# MOSFTET_Driver_block.net
KiCad netlist of a schematic drawn in Altium Designer
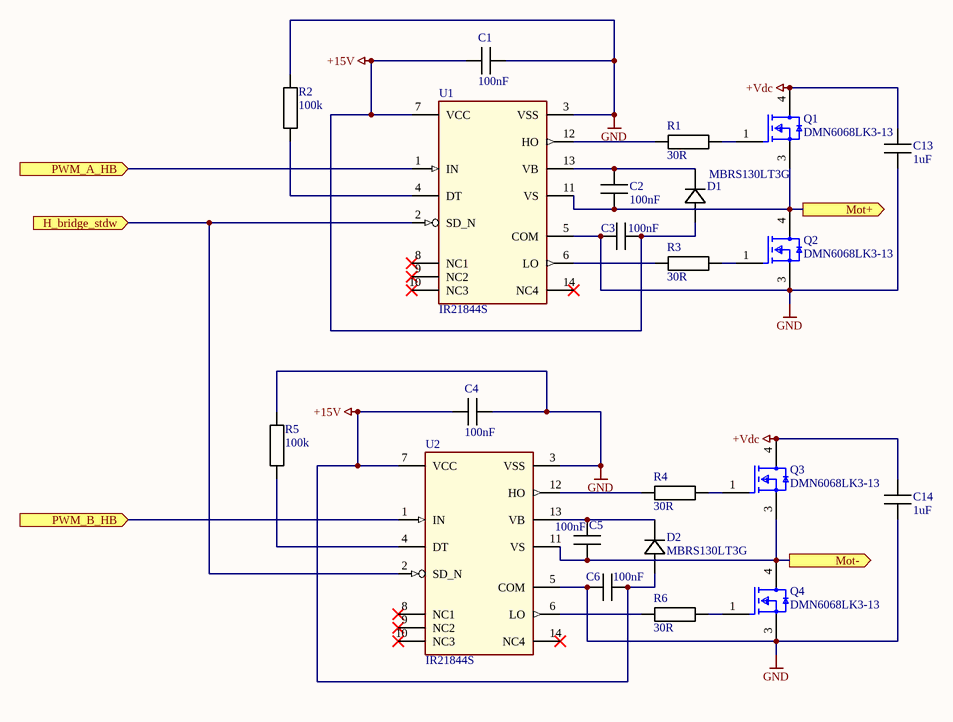
[diagram p0: MOSFTET_Driver_block.SchDoc]

(export (version "E")
  (design (tool "Eeschema 10.0.6"))
  (components
    (comp (ref "C1")
      (value "100nF")
      (footprint "CAPC1608X08M")
      (description "CAPC 100nF X7R 50V 10% 1608 (0603 INCH)")
      (fields (field (name "VOLTAGE") "50V") (field (name "MANUFACTURER") "TDK"))
      (libsource (lib "ETML-ES") (part "CAP"))
    )
    (comp (ref "C2")
      (value "100nF")
      (footprint "CAPC1608X08M")
      (description "CAPC 100nF X7R 50V 10% 1608 (0603 INCH)")
      (fields (field (name "VOLTAGE") "50V") (field (name "MANUFACTURER") "TDK"))
      (libsource (lib "ETML-ES") (part "CAP"))
    )
    (comp (ref "C3")
      (value "100nF")
      (footprint "CAPC1608X08M")
      (description "CAPC 100nF X7R 50V 10% 1608 (0603 INCH)")
      (fields (field (name "VOLTAGE") "50V") (field (name "MANUFACTURER") "TDK"))
      (libsource (lib "ETML-ES") (part "CAP"))
    )
    (comp (ref "C4")
      (value "100nF")
      (footprint "CAPC1608X08M")
      (description "CAPC 100nF X7R 50V 10% 1608 (0603 INCH)")
      (fields (field (name "VOLTAGE") "50V") (field (name "MANUFACTURER") "TDK"))
      (libsource (lib "ETML-ES") (part "CAP"))
    )
    (comp (ref "C5")
      (value "100nF")
      (footprint "CAPC1608X08M")
      (description "CAPC 100nF X7R 50V 10% 1608 (0603 INCH)")
      (fields (field (name "VOLTAGE") "50V") (field (name "MANUFACTURER") "TDK"))
      (libsource (lib "ETML-ES") (part "CAP"))
    )
    (comp (ref "C6")
      (value "100nF")
      (footprint "CAPC1608X08M")
      (description "CAPC 100nF X7R 50V 10% 1608 (0603 INCH)")
      (fields (field (name "VOLTAGE") "50V") (field (name "MANUFACTURER") "TDK"))
      (libsource (lib "ETML-ES") (part "CAP"))
    )
    (comp (ref "C13")
      (value "1uF")
      (footprint "CAPC2012X08M")
      (description "CAPC 1uF X5R 25V 10% 2012 (0805 INCH)")
      (fields (field (name "MANUFACTURER") "TDK") (field (name "TOLERANCE") "±10%"))
      (libsource (lib "ETML-ES") (part "CAP"))
    )
    (comp (ref "C14")
      (value "1uF")
      (footprint "CAPC2012X08M")
      (description "CAPC 1uF X5R 25V 10% 2012 (0805 INCH)")
      (fields (field (name "MANUFACTURER") "TDK") (field (name "TOLERANCE") "±10%"))
      (libsource (lib "ETML-ES") (part "CAP"))
    )
    (comp (ref "D1")
      (value "MBRS130LT3G")
      (footprint "DIODE_SMB_2L_ONS")
      (description "Description")
      (fields (field (name "COPYRIGHT") "Copyright (C) 2025 Ultra Librarian. All rights reserved."))
      (libsource (lib "MBRS130LT3G") (part "MBRS130LT3G"))
    )
    (comp (ref "D2")
      (value "MBRS130LT3G")
      (footprint "DIODE_SMB_2L_ONS")
      (description "Description")
      (fields (field (name "COPYRIGHT") "Copyright (C) 2025 Ultra Librarian. All rights reserved."))
      (libsource (lib "MBRS130LT3G") (part "MBRS130LT3G"))
    )
    (comp (ref "Q1")
      (value "DMN6068LK3-13")
      (footprint "FP-TO252_DPAK-MFG")
      (description "MOSFET N-CH 60V 6A DPAK")
      (fields
        (field (name "OCTOPART") "https://octopart.com/dmn6068lk3-13-diodes+inc.-17947797")
        (field (name "MANUFACTURER") "Diodes Inc.")
      )
      (libsource (lib "Altium Content Vault") (part "86656c45bbbddc162aead764a772c09"))
    )
    (comp (ref "Q2")
      (value "DMN6068LK3-13")
      (footprint "FP-TO252_DPAK-MFG")
      (description "MOSFET N-CH 60V 6A DPAK")
      (fields
        (field (name "OCTOPART") "https://octopart.com/dmn6068lk3-13-diodes+inc.-17947797")
        (field (name "MANUFACTURER") "Diodes Inc.")
      )
      (libsource (lib "Altium Content Vault") (part "86656c45bbbddc162aead764a772c09"))
    )
    (comp (ref "Q3")
      (value "DMN6068LK3-13")
      (footprint "FP-TO252_DPAK-MFG")
      (description "MOSFET N-CH 60V 6A DPAK")
      (fields
        (field (name "OCTOPART") "https://octopart.com/dmn6068lk3-13-diodes+inc.-17947797")
        (field (name "MANUFACTURER") "Diodes Inc.")
      )
      (libsource (lib "Altium Content Vault") (part "86656c45bbbddc162aead764a772c09"))
    )
    (comp (ref "Q4")
      (value "DMN6068LK3-13")
      (footprint "FP-TO252_DPAK-MFG")
      (description "MOSFET N-CH 60V 6A DPAK")
      (fields
        (field (name "OCTOPART") "https://octopart.com/dmn6068lk3-13-diodes+inc.-17947797")
        (field (name "MANUFACTURER") "Diodes Inc.")
      )
      (libsource (lib "Altium Content Vault") (part "86656c45bbbddc162aead764a772c09"))
    )
    (comp (ref "R1")
      (value "30R")
      (footprint "RESC2012X06M")
      (description "RES 100ohm  ±1% 0.125W 2012 (0805 INCH)")
      (fields (field (name "TOLERANCE") "±1%") (field (name "VOLTAGE") "150V"))
      (libsource (lib "ETML-ES") (part "RES"))
    )
    (comp (ref "R2")
      (value "100k")
      (footprint "RESC2012X06M")
      (description "RES 100kohm  ±1% 0.125W 2012 (0805 INCH)")
      (fields (field (name "MANUFACTURER") "Yageo") (field (name "VOLTAGE") "150V"))
      (libsource (lib "ETML-ES") (part "RES"))
    )
    (comp (ref "R3")
      (value "30R")
      (footprint "RESC2012X06M")
      (description "RES 100ohm  ±1% 0.125W 2012 (0805 INCH)")
      (fields (field (name "TOLERANCE") "±1%") (field (name "VOLTAGE") "150V"))
      (libsource (lib "ETML-ES") (part "RES"))
    )
    (comp (ref "R4")
      (value "30R")
      (footprint "RESC2012X06M")
      (description "RES 100ohm  ±1% 0.125W 2012 (0805 INCH)")
      (fields (field (name "TOLERANCE") "±1%") (field (name "VOLTAGE") "150V"))
      (libsource (lib "ETML-ES") (part "RES"))
    )
    (comp (ref "R5")
      (value "100k")
      (footprint "RESC2012X06M")
      (description "RES 100kohm  ±1% 0.125W 2012 (0805 INCH)")
      (fields (field (name "MANUFACTURER") "Yageo") (field (name "VOLTAGE") "150V"))
      (libsource (lib "ETML-ES") (part "RES"))
    )
    (comp (ref "R6")
      (value "30R")
      (footprint "RESC2012X06M")
      (description "RES 100ohm  ±1% 0.125W 2012 (0805 INCH)")
      (fields (field (name "TOLERANCE") "±1%") (field (name "VOLTAGE") "150V"))
      (libsource (lib "ETML-ES") (part "RES"))
    )
    (comp (ref "U1")
      (value "IR21844S")
      (footprint "SOIC127P600X175-14N-12-V")
      (description "Half-bridge gate driver with integrated bootstrap diode")
      (libsource (lib "IR21844S") (part "IR21844S"))
    )
    (comp (ref "U2")
      (value "IR21844S")
      (footprint "SOIC127P600X175-14N-12-V")
      (description "Half-bridge gate driver with integrated bootstrap diode")
      (libsource (lib "IR21844S") (part "IR21844S"))
    )
  )
  (nets
    (net (code "1") (name "+15V") (class "Default")
      (node (ref "C1") (pin "2") (pinfunction "2_2") (pintype "passive"))
      (node (ref "C3") (pin "1") (pinfunction "1_1") (pintype "passive"))
      (node (ref "C4") (pin "2") (pinfunction "2_2") (pintype "passive"))
      (node (ref "C6") (pin "1") (pinfunction "1_1") (pintype "passive"))
      (node (ref "D1") (pin "2") (pinfunction "2_2") (pintype "passive"))
      (node (ref "D2") (pin "2") (pinfunction "2_2") (pintype "passive"))
      (node (ref "U1") (pin "7") (pinfunction "VCC_7") (pintype "power_in"))
      (node (ref "U2") (pin "7") (pinfunction "VCC_7") (pintype "power_in"))
    )
    (net (code "2") (name "+Vdc") (class "Default")
      (node (ref "C13") (pin "2") (pinfunction "2_2") (pintype "passive"))
      (node (ref "C14") (pin "2") (pinfunction "2_2") (pintype "passive"))
      (node (ref "Q1") (pin "4") (pinfunction "D_4") (pintype "passive"))
      (node (ref "Q3") (pin "4") (pinfunction "D_4") (pintype "passive"))
    )
    (net (code "3") (name "/H_bridge_stdw") (class "Default")
      (node (ref "U1") (pin "2") (pinfunction "SD_N_2") (pintype "input"))
      (node (ref "U2") (pin "2") (pinfunction "SD_N_2") (pintype "input"))
    )
    (net (code "4") (name "/Mot+") (class "Default")
      (node (ref "C2") (pin "2") (pinfunction "2_2") (pintype "passive"))
      (node (ref "Q1") (pin "3") (pinfunction "S_3") (pintype "passive"))
      (node (ref "Q2") (pin "4") (pinfunction "D_4") (pintype "passive"))
      (node (ref "U1") (pin "11") (pinfunction "VS_11") (pintype "power_in"))
    )
    (net (code "5") (name "/Mot-") (class "Default")
      (node (ref "C5") (pin "1") (pinfunction "1_1") (pintype "passive"))
      (node (ref "Q3") (pin "3") (pinfunction "S_3") (pintype "passive"))
      (node (ref "Q4") (pin "4") (pinfunction "D_4") (pintype "passive"))
      (node (ref "U2") (pin "11") (pinfunction "VS_11") (pintype "power_in"))
    )
    (net (code "6") (name "/PWM_A_HB") (class "Default")
      (node (ref "U1") (pin "1") (pinfunction "IN_1") (pintype "input"))
    )
    (net (code "7") (name "/PWM_B_HB") (class "Default")
      (node (ref "U2") (pin "1") (pinfunction "IN_1") (pintype "input"))
    )
    (net (code "8") (name "GND") (class "Default")
      (node (ref "C1") (pin "1") (pinfunction "1_1") (pintype "passive"))
      (node (ref "C13") (pin "1") (pinfunction "1_1") (pintype "passive"))
      (node (ref "C14") (pin "1") (pinfunction "1_1") (pintype "passive"))
      (node (ref "C3") (pin "2") (pinfunction "2_2") (pintype "passive"))
      (node (ref "C4") (pin "1") (pinfunction "1_1") (pintype "passive"))
      (node (ref "C6") (pin "2") (pinfunction "2_2") (pintype "passive"))
      (node (ref "Q2") (pin "3") (pinfunction "S_3") (pintype "passive"))
      (node (ref "Q4") (pin "3") (pinfunction "S_3") (pintype "passive"))
      (node (ref "R2") (pin "2") (pinfunction "2_2") (pintype "passive"))
      (node (ref "R5") (pin "2") (pinfunction "2_2") (pintype "passive"))
      (node (ref "U1") (pin "3") (pinfunction "VSS_3") (pintype "power_in"))
      (node (ref "U1") (pin "5") (pinfunction "COM_5") (pintype "power_in"))
      (node (ref "U2") (pin "3") (pinfunction "VSS_3") (pintype "power_in"))
      (node (ref "U2") (pin "5") (pinfunction "COM_5") (pintype "power_in"))
    )
    (net (code "9") (name "Net-(Q1-G)") (class "Default")
      (node (ref "Q1") (pin "1") (pinfunction "G_1") (pintype "passive"))
      (node (ref "R1") (pin "2") (pinfunction "2_2") (pintype "passive"))
    )
    (net (code "10") (name "Net-(Q2-G)") (class "Default")
      (node (ref "Q2") (pin "1") (pinfunction "G_1") (pintype "passive"))
      (node (ref "R3") (pin "2") (pinfunction "2_2") (pintype "passive"))
    )
    (net (code "11") (name "Net-(Q3-G)") (class "Default")
      (node (ref "Q3") (pin "1") (pinfunction "G_1") (pintype "passive"))
      (node (ref "R4") (pin "2") (pinfunction "2_2") (pintype "passive"))
    )
    (net (code "12") (name "Net-(Q4-G)") (class "Default")
      (node (ref "Q4") (pin "1") (pinfunction "G_1") (pintype "passive"))
      (node (ref "R6") (pin "2") (pinfunction "2_2") (pintype "passive"))
    )
    (net (code "13") (name "Net-(U1-DT)") (class "Default")
      (node (ref "R2") (pin "1") (pinfunction "1_1") (pintype "passive"))
      (node (ref "U1") (pin "4") (pinfunction "DT_4") (pintype "power_in"))
    )
    (net (code "14") (name "Net-(U1-HO)") (class "Default")
      (node (ref "R1") (pin "1") (pinfunction "1_1") (pintype "passive"))
      (node (ref "U1") (pin "12") (pinfunction "HO_12") (pintype "output"))
    )
    (net (code "15") (name "Net-(U1-LO)") (class "Default")
      (node (ref "R3") (pin "1") (pinfunction "1_1") (pintype "passive"))
      (node (ref "U1") (pin "6") (pinfunction "LO_6") (pintype "output"))
    )
    (net (code "16") (name "Net-(U1-VB)") (class "Default")
      (node (ref "C2") (pin "1") (pinfunction "1_1") (pintype "passive"))
      (node (ref "D1") (pin "1") (pinfunction "1_1") (pintype "passive"))
      (node (ref "U1") (pin "13") (pinfunction "VB_13") (pintype "power_in"))
    )
    (net (code "17") (name "Net-(U2-DT)") (class "Default")
      (node (ref "R5") (pin "1") (pinfunction "1_1") (pintype "passive"))
      (node (ref "U2") (pin "4") (pinfunction "DT_4") (pintype "power_in"))
    )
    (net (code "18") (name "Net-(U2-HO)") (class "Default")
      (node (ref "R4") (pin "1") (pinfunction "1_1") (pintype "passive"))
      (node (ref "U2") (pin "12") (pinfunction "HO_12") (pintype "output"))
    )
    (net (code "19") (name "Net-(U2-LO)") (class "Default")
      (node (ref "R6") (pin "1") (pinfunction "1_1") (pintype "passive"))
      (node (ref "U2") (pin "6") (pinfunction "LO_6") (pintype "output"))
    )
    (net (code "20") (name "Net-(U2-VB)") (class "Default")
      (node (ref "C5") (pin "2") (pinfunction "2_2") (pintype "passive"))
      (node (ref "D2") (pin "1") (pinfunction "1_1") (pintype "passive"))
      (node (ref "U2") (pin "13") (pinfunction "VB_13") (pintype "power_in"))
    )
    (net (code "21") (name "unconnected-(U1-NC1-Pad8)") (class "Default")
      (node (ref "U1") (pin "8") (pinfunction "NC1_8") (pintype "passive+no_connect"))
    )
    (net (code "22") (name "unconnected-(U1-NC2-Pad9)") (class "Default")
      (node (ref "U1") (pin "9") (pinfunction "NC2_9") (pintype "passive+no_connect"))
    )
    (net (code "23") (name "unconnected-(U1-NC3-Pad10)") (class "Default")
      (node (ref "U1") (pin "10") (pinfunction "NC3_10") (pintype "passive+no_connect"))
    )
    (net (code "24") (name "unconnected-(U1-NC4-Pad14)") (class "Default")
      (node (ref "U1") (pin "14") (pinfunction "NC4_14") (pintype "passive+no_connect"))
    )
    (net (code "25") (name "unconnected-(U2-NC1-Pad8)") (class "Default")
      (node (ref "U2") (pin "8") (pinfunction "NC1_8") (pintype "passive+no_connect"))
    )
    (net (code "26") (name "unconnected-(U2-NC2-Pad9)") (class "Default")
      (node (ref "U2") (pin "9") (pinfunction "NC2_9") (pintype "passive+no_connect"))
    )
    (net (code "27") (name "unconnected-(U2-NC3-Pad10)") (class "Default")
      (node (ref "U2") (pin "10") (pinfunction "NC3_10") (pintype "passive+no_connect"))
    )
    (net (code "28") (name "unconnected-(U2-NC4-Pad14)") (class "Default")
      (node (ref "U2") (pin "14") (pinfunction "NC4_14") (pintype "passive+no_connect"))
    )
  )
)
